# ESP32.net
KiCad netlist of a schematic drawn in Altium Designer
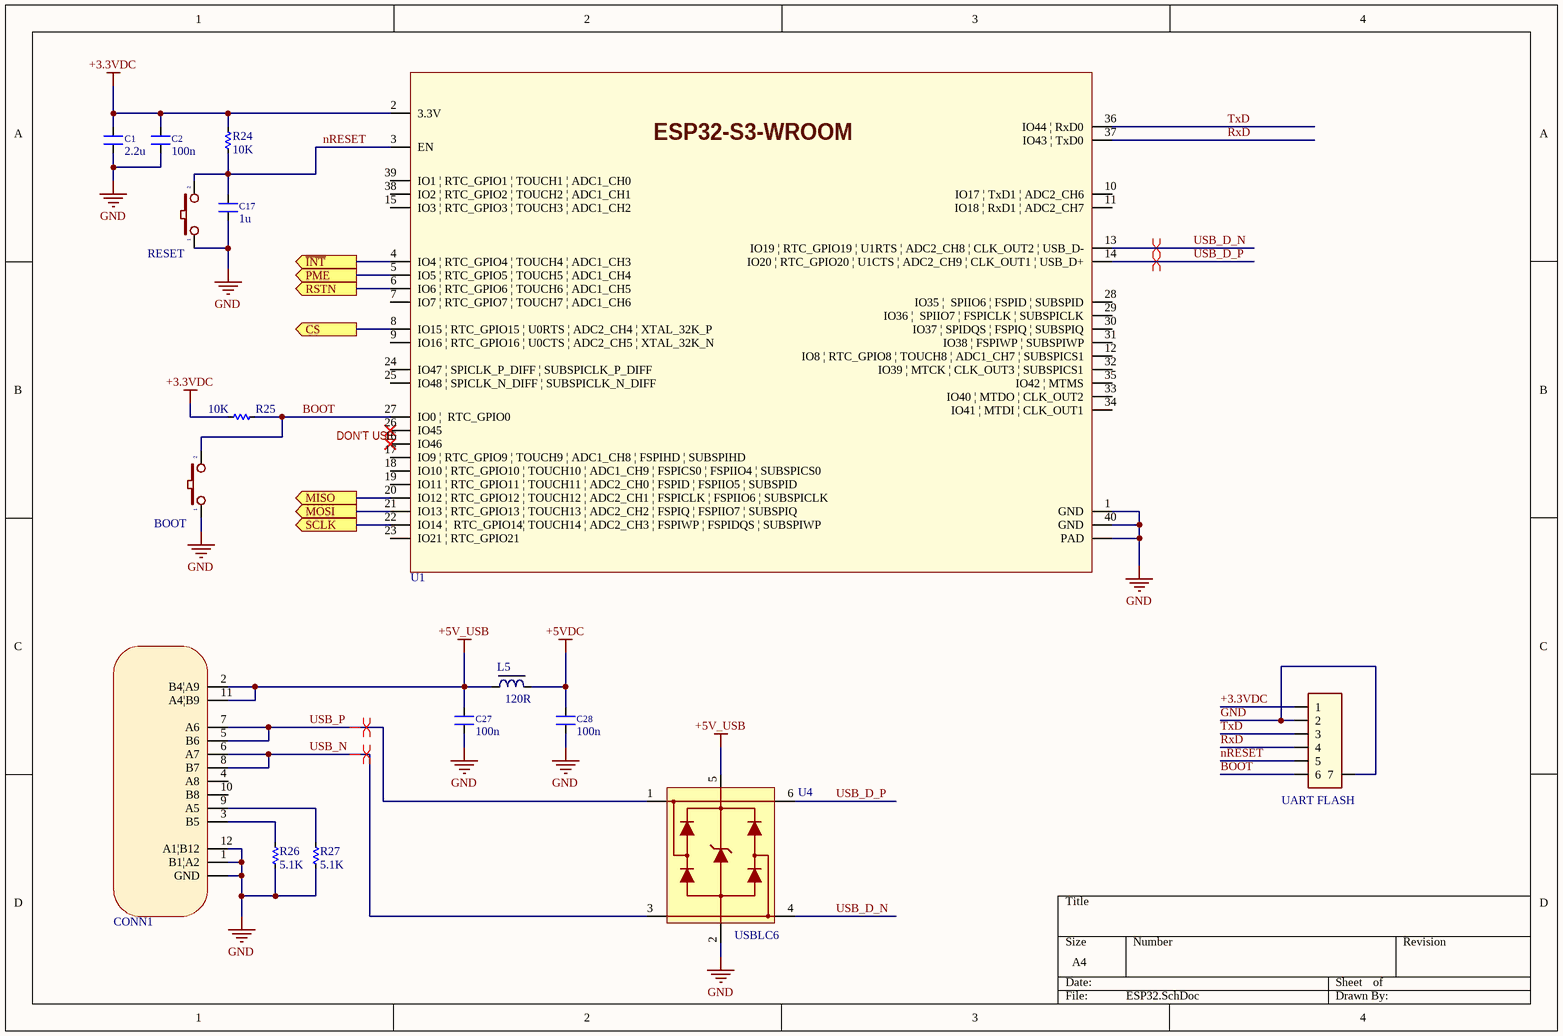
[diagram p0: ESP32.SchDoc]

(export (version "E")
  (design (tool "Eeschema 10.0.6"))
  (components
    (comp (ref "BOOT")
      (value "BUTTON1")
      (footprint "SW-SMD - 3x4")
      (libsource (lib "Sang_Library") (part "BUTTON1"))
    )
    (comp (ref "C1")
      (value "2.2u")
      (footprint "CN-SMD-0805")
      (description "CAP SMD")
      (fields (field (name "DESIGNED BY") "VanDungEvn"))
      (libsource (lib "Sang_Library") (part "CAP SMD"))
    )
    (comp (ref "C2")
      (value "100n")
      (footprint "CN-SMD-0603")
      (description "CAP SMD")
      (fields (field (name "DESIGNED BY") "VanDungEvn"))
      (libsource (lib "Sang_Library") (part "CAP SMD"))
    )
    (comp (ref "C17")
      (value "1u")
      (footprint "CN-SMD-0603")
      (description "CAP SMD")
      (fields (field (name "DESIGNED BY") "VanDungEvn"))
      (libsource (lib "Sang_Library") (part "CAP SMD"))
    )
    (comp (ref "C27")
      (value "100n")
      (footprint "CN-SMD-0603")
      (description "CAP SMD")
      (fields (field (name "DESIGNED BY") "VanDungEvn"))
      (libsource (lib "Sang_Library") (part "CAP SMD"))
    )
    (comp (ref "C28")
      (value "100n")
      (footprint "CN-SMD-0603")
      (description "CAP SMD")
      (fields (field (name "DESIGNED BY") "VanDungEvn"))
      (libsource (lib "Sang_Library") (part "CAP SMD"))
    )
    (comp (ref "CONN1")
      (value "USB-C3.1 12PIN")
      (footprint "TYPE-C-31-M-12")
      (libsource (lib "Huan") (part "USB-C3.1 12PIN"))
    )
    (comp (ref "L5")
      (value "120R")
      (footprint "IN-SMD-0603")
      (description "inductor-SMD")
      (libsource (lib "Sang_Library") (part "inductor-SMD"))
    )
    (comp (ref "R24")
      (value "10K")
      (footprint "RES-SMD-0603")
      (description "Resistor")
      (fields
        (field (name "MANUFACTURER") "Generic Components")
        (field (name "PUBLISHER") "Altium Hobart Technology Centre")
      )
      (libsource (lib "Sang_Library") (part "Res-SMD"))
    )
    (comp (ref "R25")
      (value "10K")
      (footprint "RES-SMD-0603")
      (description "Resistor")
      (fields
        (field (name "MANUFACTURER") "Generic Components")
        (field (name "PUBLISHER") "Altium Hobart Technology Centre")
      )
      (libsource (lib "Sang_Library") (part "Res-SMD"))
    )
    (comp (ref "R26")
      (value "5.1K")
      (footprint "RES-SMD-0603")
      (description "Resistor")
      (fields
        (field (name "MANUFACTURER") "Generic Components")
        (field (name "PUBLISHER") "Altium Hobart Technology Centre")
      )
      (libsource (lib "Sang_Library") (part "Res-SMD"))
    )
    (comp (ref "R27")
      (value "5.1K")
      (footprint "RES-SMD-0603")
      (description "Resistor")
      (fields
        (field (name "MANUFACTURER") "Generic Components")
        (field (name "PUBLISHER") "Altium Hobart Technology Centre")
      )
      (libsource (lib "Sang_Library") (part "Res-SMD"))
    )
    (comp (ref "RESET")
      (value "BUTTON1")
      (footprint "SW-SMD - 3x4")
      (libsource (lib "Sang_Library") (part "BUTTON1"))
    )
    (comp (ref "U1")
      (value "ESP32 S3")
      (footprint "ESP32-S3-WROOM-1/1U")
      (libsource (lib "Huan") (part "ESP32 S3"))
    )
    (comp (ref "U4")
      (value "USBLC6")
      (footprint "SOT23-6")
      (description "USB ESD")
      (libsource (lib "Huan") (part "USBLC6"))
    )
    (comp (ref "UART FLASH")
      (value "CONNECTOR 6P")
      (footprint "JST-PH2.0_6P")
      (libsource (lib "Huan") (part "CONNECTOR 6P"))
    )
  )
  (nets
    (net (code "1") (name "+3.3VDC") (class "Default")
      (node (ref "C1") (pin "2") (pinfunction "2_2") (pintype "passive"))
      (node (ref "C2") (pin "2") (pinfunction "2_2") (pintype "passive"))
      (node (ref "R24") (pin "2") (pinfunction "2_2") (pintype "passive"))
      (node (ref "R25") (pin "2") (pinfunction "2_2") (pintype "passive"))
      (node (ref "U1") (pin "2") (pinfunction "3.3V_2") (pintype "passive"))
      (node (ref "UART FLASH") (pin "1") (pinfunction "1_1") (pintype "passive"))
    )
    (net (code "2") (name "+5VDC") (class "Default")
      (node (ref "C28") (pin "2") (pinfunction "2_2") (pintype "passive"))
      (node (ref "L5") (pin "2") (pinfunction "2_2") (pintype "passive"))
    )
    (net (code "3") (name "+5V_USB") (class "Default")
      (node (ref "C27") (pin "2") (pinfunction "2_2") (pintype "passive"))
      (node (ref "CONN1") (pin "11") (pinfunction "A4¦B9_11") (pintype "passive"))
      (node (ref "CONN1") (pin "2") (pinfunction "B4¦A9_2") (pintype "passive"))
      (node (ref "L5") (pin "1") (pinfunction "1_1") (pintype "passive"))
      (node (ref "U4") (pin "5") (pintype "passive"))
    )
    (net (code "4") (name "/BOOT") (class "Default")
      (node (ref "BOOT") (pin "2") (pinfunction "2_2") (pintype "passive"))
      (node (ref "R25") (pin "1") (pinfunction "1_1") (pintype "passive"))
      (node (ref "U1") (pin "27") (pinfunction "IO0_¦__RTC_GPIO0_27") (pintype "passive"))
      (node (ref "UART FLASH") (pin "6") (pinfunction "6_6") (pintype "passive"))
    )
    (net (code "5") (name "/CS") (class "Default")
      (node (ref "U1") (pin "8") (pinfunction "IO15_¦_RTC_GPIO15_¦_U0RTS_¦_ADC2_CH4_¦_XTAL_32K_P_8") (pintype "passive"))
    )
    (net (code "6") (name "/MISO") (class "Default")
      (node (ref "U1") (pin "20") (pinfunction "IO12_¦_RTC_GPIO12_¦_TOUCH12_¦_ADC2_CH1_¦_FSPICLK_¦_FSPIIO6_¦_SUBSPICLK_20") (pintype "passive"))
    )
    (net (code "7") (name "/MOSI") (class "Default")
      (node (ref "U1") (pin "21") (pinfunction "IO13_¦_RTC_GPIO13_¦_TOUCH13_¦_ADC2_CH2_¦_FSPIQ_¦_FSPIIO7_¦_SUBSPIQ_21") (pintype "passive"))
    )
    (net (code "8") (name "/PME") (class "Default")
      (node (ref "U1") (pin "5") (pinfunction "IO5_¦_RTC_GPIO5_¦_TOUCH5_¦_ADC1_CH4_5") (pintype "passive"))
    )
    (net (code "9") (name "/RSTN") (class "Default")
      (node (ref "U1") (pin "6") (pinfunction "IO6_¦_RTC_GPIO6_¦_TOUCH6_¦_ADC1_CH5_6") (pintype "passive"))
    )
    (net (code "10") (name "/RxD") (class "Default")
      (node (ref "U1") (pin "37") (pinfunction "IO43_¦_TxD0_37") (pintype "passive"))
      (node (ref "UART FLASH") (pin "4") (pinfunction "4_4") (pintype "passive"))
    )
    (net (code "11") (name "/SCLK") (class "Default")
      (node (ref "U1") (pin "22") (pinfunction "IO14_¦__RTC_GPIO14¦_TOUCH14_¦_ADC2_CH3_¦_FSPIWP_¦_FSPIDQS_¦_SUBSPIWP_22") (pintype "passive"))
    )
    (net (code "12") (name "/TxD") (class "Default")
      (node (ref "U1") (pin "36") (pinfunction "IO44_¦_RxD0_36") (pintype "passive"))
      (node (ref "UART FLASH") (pin "3") (pinfunction "3_3") (pintype "passive"))
    )
    (net (code "13") (name "/USB_D_N") (class "Default")
      (node (ref "U1") (pin "13") (pinfunction "IO19_¦_RTC_GPIO19_¦_U1RTS_¦_ADC2_CH8_¦_CLK_OUT2_¦_USB_D-_13") (pintype "passive"))
      (node (ref "U4") (pin "4") (pintype "passive"))
    )
    (net (code "14") (name "/USB_D_P") (class "Default")
      (node (ref "U1") (pin "14") (pinfunction "IO20_¦_RTC_GPIO20_¦_U1CTS_¦_ADC2_CH9_¦_CLK_OUT1_¦_USB_D+_14") (pintype "passive"))
      (node (ref "U4") (pin "6") (pintype "passive"))
    )
    (net (code "15") (name "/USB_N") (class "Default")
      (node (ref "CONN1") (pin "6") (pinfunction "A7_6") (pintype "passive"))
      (node (ref "CONN1") (pin "8") (pinfunction "B7_8") (pintype "passive"))
      (node (ref "U4") (pin "3") (pintype "passive"))
    )
    (net (code "16") (name "/USB_P") (class "Default")
      (node (ref "CONN1") (pin "5") (pinfunction "B6_5") (pintype "passive"))
      (node (ref "CONN1") (pin "7") (pinfunction "A6_7") (pintype "passive"))
      (node (ref "U4") (pin "1") (pintype "passive"))
    )
    (net (code "17") (name "/nRESET") (class "Default")
      (node (ref "C17") (pin "2") (pinfunction "2_2") (pintype "passive"))
      (node (ref "R24") (pin "1") (pinfunction "1_1") (pintype "passive"))
      (node (ref "RESET") (pin "2") (pinfunction "2_2") (pintype "passive"))
      (node (ref "U1") (pin "3") (pinfunction "EN_3") (pintype "passive"))
      (node (ref "UART FLASH") (pin "5") (pinfunction "5_5") (pintype "passive"))
    )
    (net (code "18") (name "/~{INT}") (class "Default")
      (node (ref "U1") (pin "4") (pinfunction "IO4_¦_RTC_GPIO4_¦_TOUCH4_¦_ADC1_CH3_4") (pintype "passive"))
    )
    (net (code "19") (name "GND") (class "Default")
      (node (ref "BOOT") (pin "1") (pinfunction "1_1") (pintype "passive"))
      (node (ref "C1") (pin "1") (pinfunction "1_1") (pintype "passive"))
      (node (ref "C17") (pin "1") (pinfunction "1_1") (pintype "passive"))
      (node (ref "C2") (pin "1") (pinfunction "1_1") (pintype "passive"))
      (node (ref "C27") (pin "1") (pinfunction "1_1") (pintype "passive"))
      (node (ref "C28") (pin "1") (pinfunction "1_1") (pintype "passive"))
      (node (ref "CONN1") (pin "1") (pinfunction "B1¦A2_1") (pintype "passive"))
      (node (ref "CONN1") (pin "12") (pinfunction "A1¦B12_12") (pintype "passive"))
      (node (ref "CONN1") (pin "GND") (pinfunction "GND_GND") (pintype "passive"))
      (node (ref "R26") (pin "2") (pinfunction "2_2") (pintype "passive"))
      (node (ref "R27") (pin "2") (pinfunction "2_2") (pintype "passive"))
      (node (ref "RESET") (pin "1") (pinfunction "1_1") (pintype "passive"))
      (node (ref "U1") (pin "1") (pinfunction "GND_1") (pintype "passive"))
      (node (ref "U1") (pin "40") (pinfunction "GND_40") (pintype "passive"))
      (node (ref "U1") (pin "PAD") (pinfunction "PAD_PAD") (pintype "passive"))
      (node (ref "U4") (pin "2") (pintype "passive"))
      (node (ref "UART FLASH") (pin "2") (pinfunction "2_2") (pintype "passive"))
      (node (ref "UART FLASH") (pin "7") (pinfunction "7_7") (pintype "passive"))
    )
    (net (code "20") (name "Net-(CONN1-A5)") (class "Default")
      (node (ref "CONN1") (pin "9") (pinfunction "A5_9") (pintype "passive"))
      (node (ref "R27") (pin "1") (pinfunction "1_1") (pintype "passive"))
    )
    (net (code "21") (name "Net-(CONN1-B5)") (class "Default")
      (node (ref "CONN1") (pin "3") (pinfunction "B5_3") (pintype "passive"))
      (node (ref "R26") (pin "1") (pinfunction "1_1") (pintype "passive"))
    )
    (net (code "22") (name "unconnected-(CONN1-A8-Pad4)") (class "Default")
      (node (ref "CONN1") (pin "4") (pinfunction "A8_4") (pintype "passive"))
    )
    (net (code "23") (name "unconnected-(CONN1-B8-Pad10)") (class "Default")
      (node (ref "CONN1") (pin "10") (pinfunction "B8_10") (pintype "passive"))
    )
    (net (code "24") (name "unconnected-(U1-IO1_¦_RTC_GPIO1_¦_TOUCH1_¦_ADC1_CH0-Pad39)") (class "Default")
      (node (ref "U1") (pin "39") (pinfunction "IO1_¦_RTC_GPIO1_¦_TOUCH1_¦_ADC1_CH0_39") (pintype "passive"))
    )
    (net (code "25") (name "unconnected-(U1-IO2_¦_RTC_GPIO2_¦_TOUCH2_¦_ADC1_CH1-Pad38)") (class "Default")
      (node (ref "U1") (pin "38") (pinfunction "IO2_¦_RTC_GPIO2_¦_TOUCH2_¦_ADC1_CH1_38") (pintype "passive"))
    )
    (net (code "26") (name "unconnected-(U1-IO3_¦_RTC_GPIO3_¦_TOUCH3_¦_ADC1_CH2-Pad15)") (class "Default")
      (node (ref "U1") (pin "15") (pinfunction "IO3_¦_RTC_GPIO3_¦_TOUCH3_¦_ADC1_CH2_15") (pintype "passive"))
    )
    (net (code "27") (name "unconnected-(U1-IO7_¦_RTC_GPIO7_¦_TOUCH7_¦_ADC1_CH6-Pad7)") (class "Default")
      (node (ref "U1") (pin "7") (pinfunction "IO7_¦_RTC_GPIO7_¦_TOUCH7_¦_ADC1_CH6_7") (pintype "passive"))
    )
    (net (code "28") (name "unconnected-(U1-IO8_¦_RTC_GPIO8_¦_TOUCH8_¦_ADC1_CH7_¦_SUBSPICS1-Pad12)") (class "Default")
      (node (ref "U1") (pin "12") (pinfunction "IO8_¦_RTC_GPIO8_¦_TOUCH8_¦_ADC1_CH7_¦_SUBSPICS1_12") (pintype "passive"))
    )
    (net (code "29") (name "unconnected-(U1-IO9_¦_RTC_GPIO9_¦_TOUCH9_¦_ADC1_CH8_¦_FSPIHD_¦_SUBSPIHD-Pad17)") (class "Default")
      (node (ref "U1") (pin "17") (pinfunction "IO9_¦_RTC_GPIO9_¦_TOUCH9_¦_ADC1_CH8_¦_FSPIHD_¦_SUBSPIHD_17") (pintype "passive"))
    )
    (net (code "30") (name "unconnected-(U1-IO10_¦_RTC_GPIO10_¦_TOUCH10_¦_ADC1_CH9_¦_FSPICS0_¦_FSPIIO4_¦_SUBSPICS0-Pad18)") (class "Default")
      (node (ref "U1") (pin "18") (pinfunction "IO10_¦_RTC_GPIO10_¦_TOUCH10_¦_ADC1_CH9_¦_FSPICS0_¦_FSPIIO4_¦_SUBSPICS0_18") (pintype "passive"))
    )
    (net (code "31") (name "unconnected-(U1-IO11_¦_RTC_GPIO11_¦_TOUCH11_¦_ADC2_CH0_¦_FSPID_¦_FSPIIO5_¦_SUBSPID-Pad19)") (class "Default")
      (node (ref "U1") (pin "19") (pinfunction "IO11_¦_RTC_GPIO11_¦_TOUCH11_¦_ADC2_CH0_¦_FSPID_¦_FSPIIO5_¦_SUBSPID_19") (pintype "passive"))
    )
    (net (code "32") (name "unconnected-(U1-IO16_¦_RTC_GPIO16_¦_U0CTS_¦_ADC2_CH5_¦_XTAL_32K_N-Pad9)") (class "Default")
      (node (ref "U1") (pin "9") (pinfunction "IO16_¦_RTC_GPIO16_¦_U0CTS_¦_ADC2_CH5_¦_XTAL_32K_N_9") (pintype "passive"))
    )
    (net (code "33") (name "unconnected-(U1-IO17_¦_TxD1_¦_ADC2_CH6-Pad10)") (class "Default")
      (node (ref "U1") (pin "10") (pinfunction "IO17_¦_TxD1_¦_ADC2_CH6_10") (pintype "passive"))
    )
    (net (code "34") (name "unconnected-(U1-IO18_¦_RxD1_¦_ADC2_CH7-Pad11)") (class "Default")
      (node (ref "U1") (pin "11") (pinfunction "IO18_¦_RxD1_¦_ADC2_CH7_11") (pintype "passive"))
    )
    (net (code "35") (name "unconnected-(U1-IO21_¦_RTC_GPIO21-Pad23)") (class "Default")
      (node (ref "U1") (pin "23") (pinfunction "IO21_¦_RTC_GPIO21_23") (pintype "passive"))
    )
    (net (code "36") (name "unconnected-(U1-IO35_¦__SPIIO6_¦_FSPID_¦_SUBSPID-Pad28)") (class "Default")
      (node (ref "U1") (pin "28") (pinfunction "IO35_¦__SPIIO6_¦_FSPID_¦_SUBSPID_28") (pintype "passive"))
    )
    (net (code "37") (name "unconnected-(U1-IO36_¦__SPIIO7_¦_FSPICLK_¦_SUBSPICLK-Pad29)") (class "Default")
      (node (ref "U1") (pin "29") (pinfunction "IO36_¦__SPIIO7_¦_FSPICLK_¦_SUBSPICLK_29") (pintype "passive"))
    )
    (net (code "38") (name "unconnected-(U1-IO37_¦_SPIDQS_¦_FSPIQ_¦_SUBSPIQ-Pad30)") (class "Default")
      (node (ref "U1") (pin "30") (pinfunction "IO37_¦_SPIDQS_¦_FSPIQ_¦_SUBSPIQ_30") (pintype "passive"))
    )
    (net (code "39") (name "unconnected-(U1-IO38_¦_FSPIWP_¦_SUBSPIWP-Pad31)") (class "Default")
      (node (ref "U1") (pin "31") (pinfunction "IO38_¦_FSPIWP_¦_SUBSPIWP_31") (pintype "passive"))
    )
    (net (code "40") (name "unconnected-(U1-IO39_¦_MTCK_¦_CLK_OUT3_¦_SUBSPICS1-Pad32)") (class "Default")
      (node (ref "U1") (pin "32") (pinfunction "IO39_¦_MTCK_¦_CLK_OUT3_¦_SUBSPICS1_32") (pintype "passive"))
    )
    (net (code "41") (name "unconnected-(U1-IO40_¦_MTDO_¦_CLK_OUT2-Pad33)") (class "Default")
      (node (ref "U1") (pin "33") (pinfunction "IO40_¦_MTDO_¦_CLK_OUT2_33") (pintype "passive"))
    )
    (net (code "42") (name "unconnected-(U1-IO41_¦_MTDI_¦_CLK_OUT1-Pad34)") (class "Default")
      (node (ref "U1") (pin "34") (pinfunction "IO41_¦_MTDI_¦_CLK_OUT1_34") (pintype "passive"))
    )
    (net (code "43") (name "unconnected-(U1-IO42_¦_MTMS-Pad35)") (class "Default")
      (node (ref "U1") (pin "35") (pinfunction "IO42_¦_MTMS_35") (pintype "passive"))
    )
    (net (code "44") (name "unconnected-(U1-IO45-Pad26)") (class "Default")
      (node (ref "U1") (pin "26") (pinfunction "IO45_26") (pintype "passive+no_connect"))
    )
    (net (code "45") (name "unconnected-(U1-IO46-Pad16)") (class "Default")
      (node (ref "U1") (pin "16") (pinfunction "IO46_16") (pintype "passive+no_connect"))
    )
    (net (code "46") (name "unconnected-(U1-IO47_¦_SPICLK_P_DIFF_¦_SUBSPICLK_P_DIFF-Pad24)") (class "Default")
      (node (ref "U1") (pin "24") (pinfunction "IO47_¦_SPICLK_P_DIFF_¦_SUBSPICLK_P_DIFF_24") (pintype "passive"))
    )
    (net (code "47") (name "unconnected-(U1-IO48_¦_SPICLK_N_DIFF_¦_SUBSPICLK_N_DIFF-Pad25)") (class "Default")
      (node (ref "U1") (pin "25") (pinfunction "IO48_¦_SPICLK_N_DIFF_¦_SUBSPICLK_N_DIFF_25") (pintype "passive"))
    )
  )
)
